# schematic.net
KiCad netlist of a schematic drawn in EAGLE
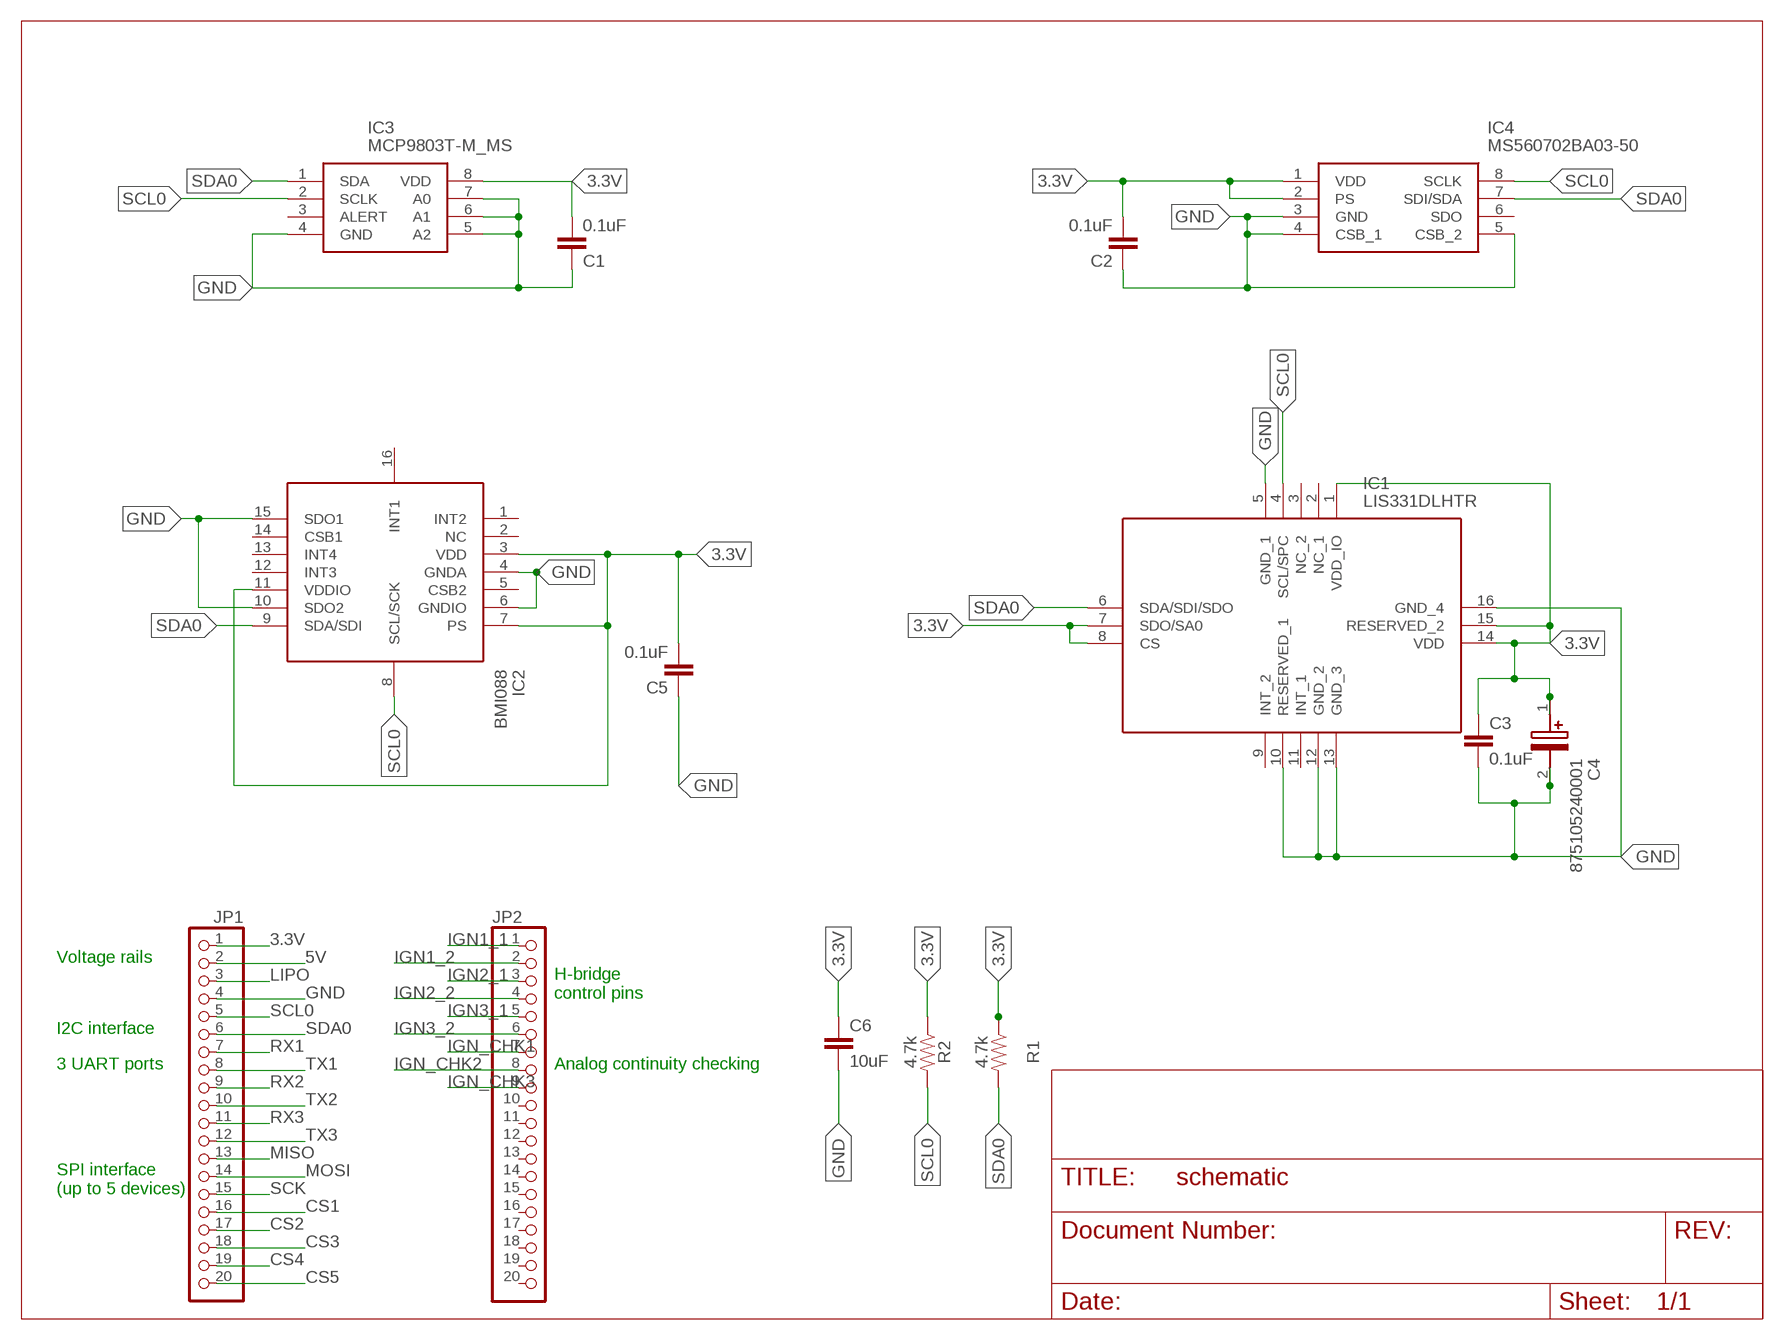
[diagram p0: schematic, sheet 1]

(export (version "E")
  (design (tool "Eeschema 10.0.6"))
  (components
    (comp (ref "C1")
      (value "0.1uF")
      (footprint "eagle-import:0805")
      (libsource (lib "eagle-import") (part "CAP-0805"))
    )
    (comp (ref "C2")
      (value "0.1uF")
      (footprint "eagle-import:0805")
      (libsource (lib "eagle-import") (part "CAP-0805"))
    )
    (comp (ref "C3")
      (value "0.1uF")
      (footprint "eagle-import:0805")
      (libsource (lib "eagle-import") (part "CAP-0805"))
    )
    (comp (ref "C4")
      (value "875105240001")
      (footprint "eagle-import:CAPAE430X550N")
      (fields (field (name "MOUSER_PART_NUMBER") "710-875105240001"))
      (libsource (lib "eagle-import") (part "875105240001"))
    )
    (comp (ref "C5")
      (value "0.1uF")
      (footprint "eagle-import:0805")
      (libsource (lib "eagle-import") (part "CAP-0805"))
    )
    (comp (ref "C6")
      (value "10uF")
      (footprint "eagle-import:0805")
      (libsource (lib "eagle-import") (part "10UF-0805-10V-10%"))
    )
    (comp (ref "IC1")
      (value "LIS331DLHTR")
      (footprint "eagle-import:LIS331DLHTR")
      (fields (field (name "MOUSER_PART_NUMBER") "511-LIS331DLHTR"))
      (libsource (lib "eagle-import") (part "LIS331DLHTR"))
    )
    (comp (ref "IC2")
      (value "BMI088")
      (footprint "eagle-import:BMI088")
      (fields (field (name "MOUSER_PART_NUMBER") "262-BMI088"))
      (libsource (lib "eagle-import") (part "BMI088"))
    )
    (comp (ref "IC3")
      (value "MCP9803T-M_MS")
      (footprint "eagle-import:SOP65P490X110-8N")
      (fields
        (field (name "ARROW_PART_NUMBER") "MCP9803T-M/MS")
        (field (name "MOUSER_PART_NUMBER") "579-MCP9803T-M/MS")
      )
      (libsource (lib "eagle-import") (part "MCP9803T-M_MS"))
    )
    (comp (ref "IC4")
      (value "MS560702BA03-50")
      (footprint "eagle-import:MS5607-02BA03")
      (fields (field (name "MOUSER_PART_NUMBER") "824-MS560702BA03-50"))
      (libsource (lib "eagle-import") (part "MS560702BA03-50"))
    )
    (comp (ref "JP1")
      (value "PINHD-1X20")
      (footprint "eagle-import:1X20")
      (libsource (lib "eagle-import") (part "PINHD-1X20"))
    )
    (comp (ref "JP2")
      (value "PINHD-1X20")
      (footprint "eagle-import:1X20")
      (libsource (lib "eagle-import") (part "PINHD-1X20"))
    )
    (comp (ref "R1")
      (value "4.7k")
      (footprint "eagle-import:0805")
      (libsource (lib "eagle-import") (part "RESISTOR0805"))
    )
    (comp (ref "R2")
      (value "4.7k")
      (footprint "eagle-import:0805")
      (libsource (lib "eagle-import") (part "RESISTOR0805"))
    )
  )
  (nets
    (net (code "1") (name "/5V") (class "Default")
      (node (ref "JP1") (pin "2") (pinfunction "2_2") (pintype "passive"))
    )
    (net (code "2") (name "/CS1") (class "Default")
      (node (ref "JP1") (pin "16") (pinfunction "16_16") (pintype "passive"))
    )
    (net (code "3") (name "/CS2") (class "Default")
      (node (ref "JP1") (pin "17") (pinfunction "17_17") (pintype "passive"))
    )
    (net (code "4") (name "/CS3") (class "Default")
      (node (ref "JP1") (pin "18") (pinfunction "18_18") (pintype "passive"))
    )
    (net (code "5") (name "/CS4") (class "Default")
      (node (ref "JP1") (pin "19") (pinfunction "19_19") (pintype "passive"))
    )
    (net (code "6") (name "/CS5") (class "Default")
      (node (ref "JP1") (pin "20") (pinfunction "20_20") (pintype "passive"))
    )
    (net (code "7") (name "/IGN1_1") (class "Default")
      (node (ref "JP2") (pin "1") (pinfunction "1_1") (pintype "passive"))
    )
    (net (code "8") (name "/IGN1_2") (class "Default")
      (node (ref "JP2") (pin "2") (pinfunction "2_2") (pintype "passive"))
    )
    (net (code "9") (name "/IGN2_1") (class "Default")
      (node (ref "JP2") (pin "3") (pinfunction "3_3") (pintype "passive"))
    )
    (net (code "10") (name "/IGN2_2") (class "Default")
      (node (ref "JP2") (pin "4") (pinfunction "4_4") (pintype "passive"))
    )
    (net (code "11") (name "/IGN3_1") (class "Default")
      (node (ref "JP2") (pin "5") (pinfunction "5_5") (pintype "passive"))
    )
    (net (code "12") (name "/IGN3_2") (class "Default")
      (node (ref "JP2") (pin "6") (pinfunction "6_6") (pintype "passive"))
    )
    (net (code "13") (name "/IGN_CHK1") (class "Default")
      (node (ref "JP2") (pin "7") (pinfunction "7_7") (pintype "passive"))
    )
    (net (code "14") (name "/IGN_CHK2") (class "Default")
      (node (ref "JP2") (pin "8") (pinfunction "8_8") (pintype "passive"))
    )
    (net (code "15") (name "/IGN_CHK3") (class "Default")
      (node (ref "JP2") (pin "9") (pinfunction "9_9") (pintype "passive"))
    )
    (net (code "16") (name "/LIPO") (class "Default")
      (node (ref "JP1") (pin "3") (pinfunction "3_3") (pintype "passive"))
    )
    (net (code "17") (name "/MISO") (class "Default")
      (node (ref "JP1") (pin "13") (pinfunction "13_13") (pintype "passive"))
    )
    (net (code "18") (name "/MOSI") (class "Default")
      (node (ref "JP1") (pin "14") (pinfunction "14_14") (pintype "passive"))
    )
    (net (code "19") (name "/RX1") (class "Default")
      (node (ref "JP1") (pin "7") (pinfunction "7_7") (pintype "passive"))
    )
    (net (code "20") (name "/RX2") (class "Default")
      (node (ref "JP1") (pin "9") (pinfunction "9_9") (pintype "passive"))
    )
    (net (code "21") (name "/RX3") (class "Default")
      (node (ref "JP1") (pin "11") (pinfunction "11_11") (pintype "passive"))
    )
    (net (code "22") (name "/SCK") (class "Default")
      (node (ref "JP1") (pin "15") (pinfunction "15_15") (pintype "passive"))
    )
    (net (code "23") (name "/TX1") (class "Default")
      (node (ref "JP1") (pin "8") (pinfunction "8_8") (pintype "passive"))
    )
    (net (code "24") (name "/TX2") (class "Default")
      (node (ref "JP1") (pin "10") (pinfunction "10_10") (pintype "passive"))
    )
    (net (code "25") (name "/TX3") (class "Default")
      (node (ref "JP1") (pin "12") (pinfunction "12_12") (pintype "passive"))
    )
    (net (code "26") (name "3.3V") (class "Default")
      (node (ref "C1") (pin "2") (pinfunction "2_2") (pintype "passive"))
      (node (ref "C2") (pin "2") (pinfunction "2_2") (pintype "passive"))
      (node (ref "C3") (pin "2") (pinfunction "2_2") (pintype "passive"))
      (node (ref "C4") (pin "1") (pinfunction "+_1") (pintype "bidirectional"))
      (node (ref "C5") (pin "2") (pinfunction "2_2") (pintype "passive"))
      (node (ref "C6") (pin "1") (pinfunction "1_1") (pintype "passive"))
      (node (ref "IC1") (pin "1") (pinfunction "VDD_IO_1") (pintype "bidirectional"))
      (node (ref "IC1") (pin "14") (pinfunction "VDD_14") (pintype "bidirectional"))
      (node (ref "IC1") (pin "15") (pinfunction "RESERVED_2_15") (pintype "bidirectional"))
      (node (ref "IC1") (pin "7") (pinfunction "SDO/SA0_7") (pintype "bidirectional"))
      (node (ref "IC1") (pin "8") (pinfunction "CS_8") (pintype "bidirectional"))
      (node (ref "IC2") (pin "11") (pinfunction "VDDIO_11") (pintype "bidirectional"))
      (node (ref "IC2") (pin "3") (pinfunction "VDD_3") (pintype "bidirectional"))
      (node (ref "IC2") (pin "7") (pinfunction "PS_7") (pintype "bidirectional"))
      (node (ref "IC3") (pin "8") (pinfunction "VDD_8") (pintype "bidirectional"))
      (node (ref "IC4") (pin "1") (pinfunction "VDD_1") (pintype "power_in"))
      (node (ref "IC4") (pin "2") (pinfunction "PS_2") (pintype "input"))
      (node (ref "JP1") (pin "1") (pinfunction "1_1") (pintype "passive"))
      (node (ref "R1") (pin "1") (pinfunction "1_1") (pintype "passive"))
      (node (ref "R2") (pin "1") (pinfunction "1_1") (pintype "passive"))
    )
    (net (code "27") (name "GND") (class "Default")
      (node (ref "C1") (pin "1") (pinfunction "1_1") (pintype "passive"))
      (node (ref "C2") (pin "1") (pinfunction "1_1") (pintype "passive"))
      (node (ref "C3") (pin "1") (pinfunction "1_1") (pintype "passive"))
      (node (ref "C4") (pin "2") (pinfunction "-_2") (pintype "bidirectional"))
      (node (ref "C5") (pin "1") (pinfunction "1_1") (pintype "passive"))
      (node (ref "C6") (pin "2") (pinfunction "2_2") (pintype "passive"))
      (node (ref "IC1") (pin "10") (pinfunction "RESERVED_1_10") (pintype "bidirectional"))
      (node (ref "IC1") (pin "12") (pinfunction "GND_2_12") (pintype "bidirectional"))
      (node (ref "IC1") (pin "13") (pinfunction "GND_3_13") (pintype "bidirectional"))
      (node (ref "IC1") (pin "16") (pinfunction "GND_4_16") (pintype "bidirectional"))
      (node (ref "IC1") (pin "5") (pinfunction "GND_1_5") (pintype "bidirectional"))
      (node (ref "IC2") (pin "10") (pinfunction "SDO2_10") (pintype "bidirectional"))
      (node (ref "IC2") (pin "15") (pinfunction "SDO1_15") (pintype "bidirectional"))
      (node (ref "IC2") (pin "4") (pinfunction "GNDA_4") (pintype "bidirectional"))
      (node (ref "IC2") (pin "6") (pinfunction "GNDIO_6") (pintype "bidirectional"))
      (node (ref "IC3") (pin "4") (pinfunction "GND_4") (pintype "bidirectional"))
      (node (ref "IC3") (pin "5") (pinfunction "A2_5") (pintype "bidirectional"))
      (node (ref "IC3") (pin "6") (pinfunction "A1_6") (pintype "bidirectional"))
      (node (ref "IC3") (pin "7") (pinfunction "A0_7") (pintype "bidirectional"))
      (node (ref "IC4") (pin "3") (pinfunction "GND_3") (pintype "power_in"))
      (node (ref "IC4") (pin "4") (pinfunction "CSB_1_4") (pintype "input"))
      (node (ref "IC4") (pin "5") (pinfunction "CSB_2_5") (pintype "input"))
      (node (ref "JP1") (pin "4") (pinfunction "4_4") (pintype "passive"))
    )
    (net (code "28") (name "SCL0") (class "Default")
      (node (ref "IC1") (pin "4") (pinfunction "SCL/SPC_4") (pintype "bidirectional"))
      (node (ref "IC2") (pin "8") (pinfunction "SCL/SCK_8") (pintype "bidirectional"))
      (node (ref "IC3") (pin "2") (pinfunction "SCLK_2") (pintype "bidirectional"))
      (node (ref "IC4") (pin "8") (pinfunction "SCLK_8") (pintype "input"))
      (node (ref "JP1") (pin "5") (pinfunction "5_5") (pintype "passive"))
      (node (ref "R2") (pin "2") (pinfunction "2_2") (pintype "passive"))
    )
    (net (code "29") (name "SDA0") (class "Default")
      (node (ref "IC1") (pin "6") (pinfunction "SDA/SDI/SDO_6") (pintype "bidirectional"))
      (node (ref "IC2") (pin "9") (pinfunction "SDA/SDI_9") (pintype "bidirectional"))
      (node (ref "IC3") (pin "1") (pinfunction "SDA_1") (pintype "bidirectional"))
      (node (ref "IC4") (pin "7") (pinfunction "SDI/SDA_7") (pintype "bidirectional"))
      (node (ref "JP1") (pin "6") (pinfunction "6_6") (pintype "passive"))
      (node (ref "R1") (pin "2") (pinfunction "2_2") (pintype "passive"))
    )
    (net (code "30") (name "unconnected-(IC1-INT_1-Pad11)") (class "Default")
      (node (ref "IC1") (pin "11") (pinfunction "INT_1_11") (pintype "bidirectional"))
    )
    (net (code "31") (name "unconnected-(IC1-INT_2-Pad9)") (class "Default")
      (node (ref "IC1") (pin "9") (pinfunction "INT_2_9") (pintype "bidirectional"))
    )
    (net (code "32") (name "unconnected-(IC1-NC_1-Pad2)") (class "Default")
      (node (ref "IC1") (pin "2") (pinfunction "NC_1_2") (pintype "bidirectional"))
    )
    (net (code "33") (name "unconnected-(IC1-NC_2-Pad3)") (class "Default")
      (node (ref "IC1") (pin "3") (pinfunction "NC_2_3") (pintype "bidirectional"))
    )
    (net (code "34") (name "unconnected-(IC2-CSB1-Pad14)") (class "Default")
      (node (ref "IC2") (pin "14") (pinfunction "CSB1_14") (pintype "bidirectional"))
    )
    (net (code "35") (name "unconnected-(IC2-CSB2-Pad5)") (class "Default")
      (node (ref "IC2") (pin "5") (pinfunction "CSB2_5") (pintype "bidirectional"))
    )
    (net (code "36") (name "unconnected-(IC2-INT1-Pad16)") (class "Default")
      (node (ref "IC2") (pin "16") (pinfunction "INT1_16") (pintype "bidirectional"))
    )
    (net (code "37") (name "unconnected-(IC2-INT2-Pad1)") (class "Default")
      (node (ref "IC2") (pin "1") (pinfunction "INT2_1") (pintype "bidirectional"))
    )
    (net (code "38") (name "unconnected-(IC2-INT3-Pad12)") (class "Default")
      (node (ref "IC2") (pin "12") (pinfunction "INT3_12") (pintype "bidirectional"))
    )
    (net (code "39") (name "unconnected-(IC2-INT4-Pad13)") (class "Default")
      (node (ref "IC2") (pin "13") (pinfunction "INT4_13") (pintype "bidirectional"))
    )
    (net (code "40") (name "unconnected-(IC2-NC-Pad2)") (class "Default")
      (node (ref "IC2") (pin "2") (pinfunction "NC_2") (pintype "no_connect"))
    )
    (net (code "41") (name "unconnected-(IC3-ALERT-Pad3)") (class "Default")
      (node (ref "IC3") (pin "3") (pinfunction "ALERT_3") (pintype "bidirectional"))
    )
    (net (code "42") (name "unconnected-(IC4-SDO-Pad6)") (class "Default")
      (node (ref "IC4") (pin "6") (pinfunction "SDO_6") (pintype "output"))
    )
    (net (code "43") (name "unconnected-(JP2-Pad10)") (class "Default")
      (node (ref "JP2") (pin "10") (pinfunction "10_10") (pintype "passive"))
    )
    (net (code "44") (name "unconnected-(JP2-Pad11)") (class "Default")
      (node (ref "JP2") (pin "11") (pinfunction "11_11") (pintype "passive"))
    )
    (net (code "45") (name "unconnected-(JP2-Pad12)") (class "Default")
      (node (ref "JP2") (pin "12") (pinfunction "12_12") (pintype "passive"))
    )
    (net (code "46") (name "unconnected-(JP2-Pad13)") (class "Default")
      (node (ref "JP2") (pin "13") (pinfunction "13_13") (pintype "passive"))
    )
    (net (code "47") (name "unconnected-(JP2-Pad14)") (class "Default")
      (node (ref "JP2") (pin "14") (pinfunction "14_14") (pintype "passive"))
    )
    (net (code "48") (name "unconnected-(JP2-Pad15)") (class "Default")
      (node (ref "JP2") (pin "15") (pinfunction "15_15") (pintype "passive"))
    )
    (net (code "49") (name "unconnected-(JP2-Pad16)") (class "Default")
      (node (ref "JP2") (pin "16") (pinfunction "16_16") (pintype "passive"))
    )
    (net (code "50") (name "unconnected-(JP2-Pad17)") (class "Default")
      (node (ref "JP2") (pin "17") (pinfunction "17_17") (pintype "passive"))
    )
    (net (code "51") (name "unconnected-(JP2-Pad18)") (class "Default")
      (node (ref "JP2") (pin "18") (pinfunction "18_18") (pintype "passive"))
    )
    (net (code "52") (name "unconnected-(JP2-Pad19)") (class "Default")
      (node (ref "JP2") (pin "19") (pinfunction "19_19") (pintype "passive"))
    )
    (net (code "53") (name "unconnected-(JP2-Pad20)") (class "Default")
      (node (ref "JP2") (pin "20") (pinfunction "20_20") (pintype "passive"))
    )
  )
)
